# MyMultisensors_rev1-1.net
KiCad netlist of a schematic drawn in EAGLE
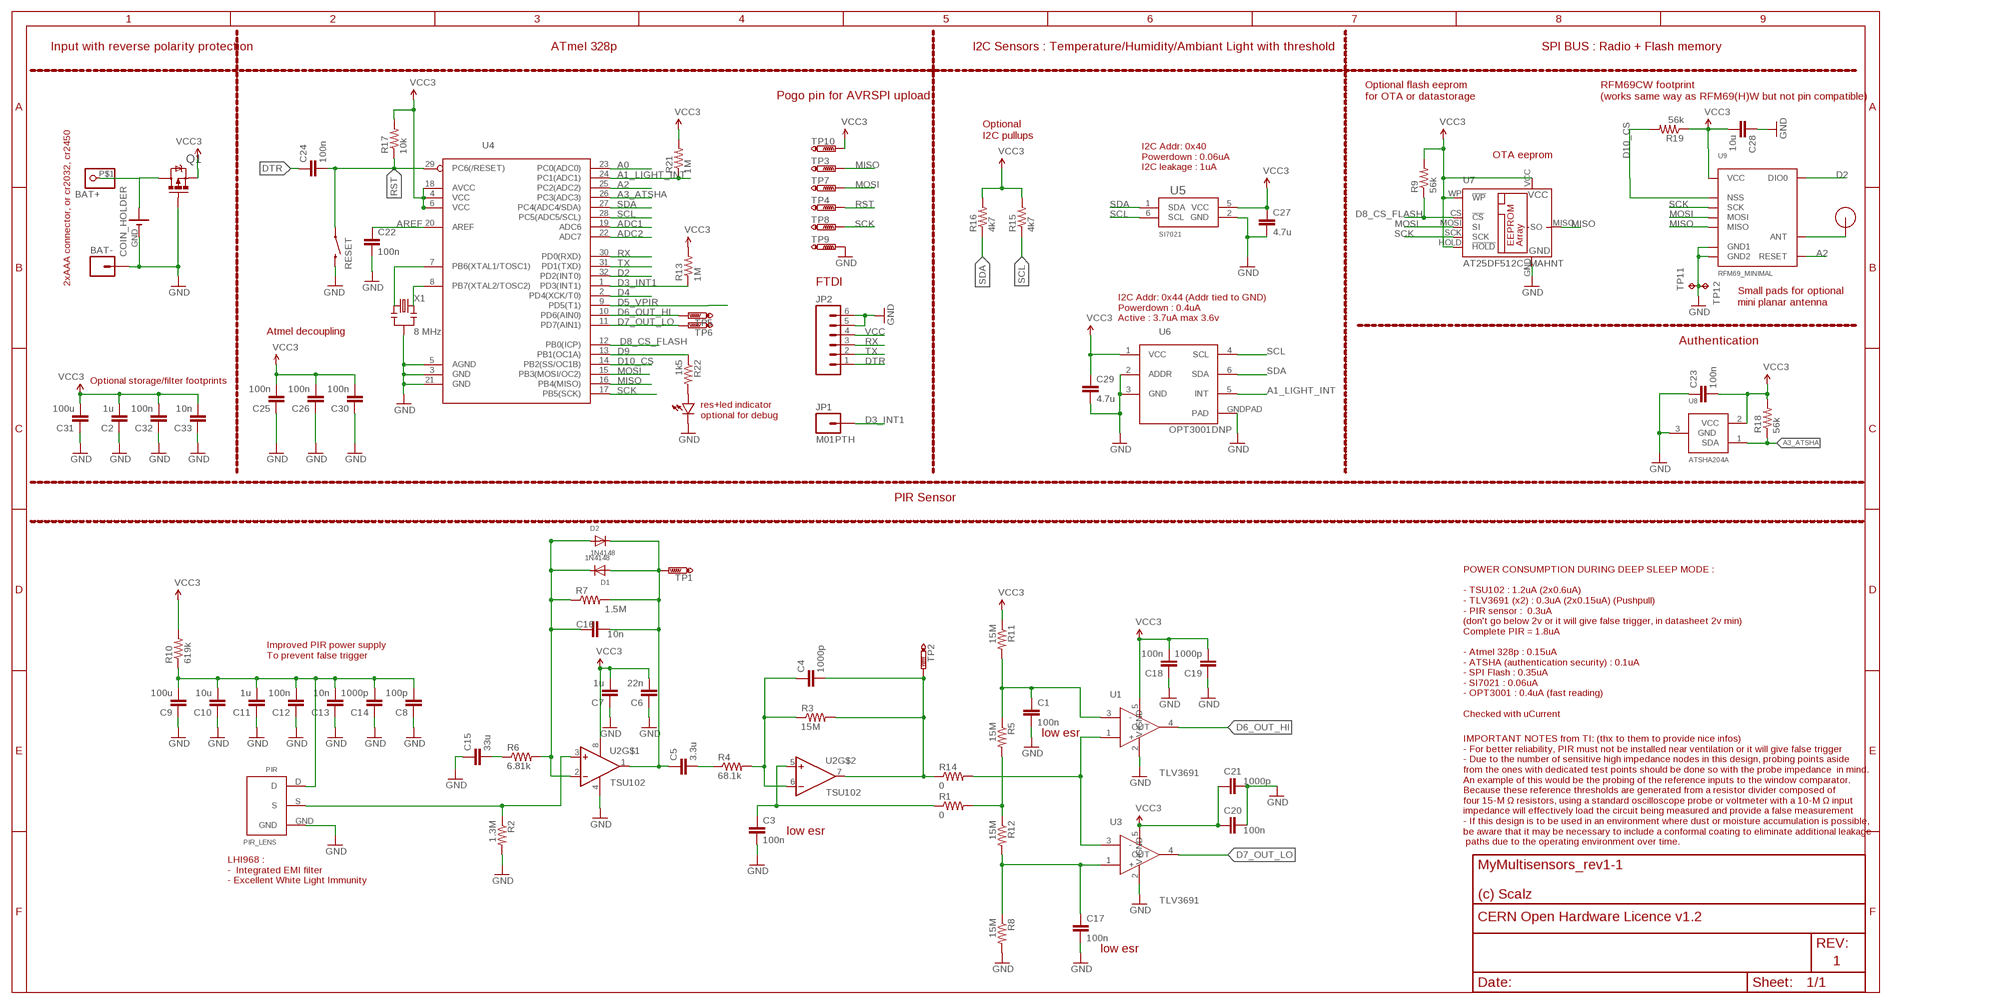
[diagram p0: schematic, sheet 1]

(export (version "E")
  (design (tool "Eeschema 10.0.6"))
  (components
    (comp (ref "ANT")
      (value "RFM12B_ANTENNA")
      (footprint "eagle-import:RFM12B-ANTENNA")
      (libsource (lib "eagle-import") (part "RFM12B_ANTENNA"))
    )
    (comp (ref "BAT+")
      (value "PINHD-1X1TOP")
      (footprint "eagle-import:1X01_ONESIDE")
      (libsource (lib "eagle-import") (part "PINHD-1X1TOP"))
    )
    (comp (ref "BAT-")
      (value "M01PTH")
      (footprint "eagle-import:1X01")
      (libsource (lib "eagle-import") (part "M01PTH"))
    )
    (comp (ref "C1")
      (value "100n")
      (footprint "eagle-import:0603-CAP")
      (libsource (lib "eagle-import") (part "CAP0603-CAP"))
    )
    (comp (ref "C2")
      (value "1u")
      (footprint "eagle-import:0805-CAP")
      (libsource (lib "eagle-import") (part "CAP0805-CAP"))
    )
    (comp (ref "C3")
      (value "100n")
      (footprint "eagle-import:0603-CAP")
      (libsource (lib "eagle-import") (part "CAP0603-CAP"))
    )
    (comp (ref "C4")
      (value "1000p")
      (footprint "eagle-import:0603-CAP")
      (libsource (lib "eagle-import") (part "CAP0603-CAP"))
    )
    (comp (ref "C5")
      (value "3.3u")
      (footprint "eagle-import:0603-CAP")
      (libsource (lib "eagle-import") (part "CAP0603-CAP"))
    )
    (comp (ref "C6")
      (value "22n")
      (footprint "eagle-import:0603-CAP")
      (libsource (lib "eagle-import") (part "CAP0603-CAP"))
    )
    (comp (ref "C7")
      (value "1u")
      (footprint "eagle-import:0603-CAP")
      (libsource (lib "eagle-import") (part "CAP0603-CAP"))
    )
    (comp (ref "C8")
      (value "100p")
      (footprint "eagle-import:0603-CAP")
      (libsource (lib "eagle-import") (part "CAP0603-CAP"))
    )
    (comp (ref "C9")
      (value "100u")
      (footprint "eagle-import:0805-CAP")
      (libsource (lib "eagle-import") (part "CAP0805-CAP"))
    )
    (comp (ref "C10")
      (value "10u")
      (footprint "eagle-import:0805-CAP")
      (libsource (lib "eagle-import") (part "CAP0805-CAP"))
    )
    (comp (ref "C11")
      (value "1u")
      (footprint "eagle-import:0603-CAP")
      (libsource (lib "eagle-import") (part "CAP0603-CAP"))
    )
    (comp (ref "C12")
      (value "100n")
      (footprint "eagle-import:0603-CAP")
      (libsource (lib "eagle-import") (part "CAP0603-CAP"))
    )
    (comp (ref "C13")
      (value "10n")
      (footprint "eagle-import:0603-CAP")
      (libsource (lib "eagle-import") (part "CAP0603-CAP"))
    )
    (comp (ref "C14")
      (value "1000p")
      (footprint "eagle-import:0603-CAP")
      (libsource (lib "eagle-import") (part "CAP0603-CAP"))
    )
    (comp (ref "C15")
      (value "33u")
      (footprint "eagle-import:0805-CAP")
      (libsource (lib "eagle-import") (part "CAP0805-CAP"))
    )
    (comp (ref "C16")
      (value "10n")
      (footprint "eagle-import:0603-CAP")
      (libsource (lib "eagle-import") (part "CAP0603-CAP"))
    )
    (comp (ref "C17")
      (value "100n")
      (footprint "eagle-import:0603-CAP")
      (libsource (lib "eagle-import") (part "CAP0603-CAP"))
    )
    (comp (ref "C18")
      (value "100n")
      (footprint "eagle-import:0603-CAP")
      (libsource (lib "eagle-import") (part "CAP0603-CAP"))
    )
    (comp (ref "C19")
      (value "1000p")
      (footprint "eagle-import:0603-CAP")
      (libsource (lib "eagle-import") (part "CAP0603-CAP"))
    )
    (comp (ref "C20")
      (value "100n")
      (footprint "eagle-import:0603-CAP")
      (libsource (lib "eagle-import") (part "CAP0603-CAP"))
    )
    (comp (ref "C21")
      (value "1000p")
      (footprint "eagle-import:0603-CAP")
      (libsource (lib "eagle-import") (part "CAP0603-CAP"))
    )
    (comp (ref "C22")
      (value "100n")
      (footprint "eagle-import:0603-CAP")
      (libsource (lib "eagle-import") (part "CAP0603-CAP"))
    )
    (comp (ref "C23")
      (value "100n")
      (footprint "eagle-import:0603-CAP")
      (libsource (lib "eagle-import") (part "CAP0603-CAP"))
    )
    (comp (ref "C24")
      (value "100n")
      (footprint "eagle-import:0805-CAP")
      (libsource (lib "eagle-import") (part "CAP0805-CAP"))
    )
    (comp (ref "C25")
      (value "100n")
      (footprint "eagle-import:0603-CAP")
      (libsource (lib "eagle-import") (part "CAP0603-CAP"))
    )
    (comp (ref "C26")
      (value "100n")
      (footprint "eagle-import:0603-CAP")
      (libsource (lib "eagle-import") (part "CAP0603-CAP"))
    )
    (comp (ref "C27")
      (value "4.7u")
      (footprint "eagle-import:0603-CAP")
      (libsource (lib "eagle-import") (part "CAP0603-CAP"))
    )
    (comp (ref "C28")
      (value "10u")
      (footprint "eagle-import:0805-CAP")
      (libsource (lib "eagle-import") (part "CAP0805-CAP"))
    )
    (comp (ref "C29")
      (value "4.7u")
      (footprint "eagle-import:0603-CAP")
      (libsource (lib "eagle-import") (part "CAP0603-CAP"))
    )
    (comp (ref "C30")
      (value "100n")
      (footprint "eagle-import:0603-CAP")
      (libsource (lib "eagle-import") (part "CAP0603-CAP"))
    )
    (comp (ref "C31")
      (value "100u")
      (footprint "eagle-import:0805-CAP")
      (libsource (lib "eagle-import") (part "CAP0805-CAP"))
    )
    (comp (ref "C32")
      (value "100n")
      (footprint "eagle-import:0603-CAP")
      (libsource (lib "eagle-import") (part "CAP0603-CAP"))
    )
    (comp (ref "C33")
      (value "10n")
      (footprint "eagle-import:0603-CAP")
      (libsource (lib "eagle-import") (part "CAP0603-CAP"))
    )
    (comp (ref "COIN_HOLDER")
      (value "CR2450_H_LOWCOSTVERTICAL_WITH_MILL")
      (footprint "eagle-import:CR2450H_LOWCOST2")
      (libsource (lib "eagle-import") (part "CR2450_H_LOWCOSTVERTICAL_WITH_MILL"))
    )
    (comp (ref "D1")
      (value "1N4148")
      (footprint "eagle-import:SOD-123")
      (libsource (lib "eagle-import") (part "DIODESOD-123"))
    )
    (comp (ref "D2")
      (value "1N4148")
      (footprint "eagle-import:SOD-123")
      (libsource (lib "eagle-import") (part "DIODESOD-123"))
    )
    (comp (ref "D3")
      (value "LED0805")
      (footprint "eagle-import:0805-LED")
      (libsource (lib "eagle-import") (part "LED0805"))
    )
    (comp (ref "JP1")
      (value "M01PTH")
      (footprint "eagle-import:1X01")
      (libsource (lib "eagle-import") (part "M01PTH"))
    )
    (comp (ref "JP2")
      (value "M06SIP")
      (footprint "eagle-import:1X06")
      (libsource (lib "eagle-import") (part "M06SIP"))
    )
    (comp (ref "PIR")
      (value "PIR_LENS")
      (footprint "eagle-import:PIR_LENS")
      (libsource (lib "eagle-import") (part "PIR_LENS"))
    )
    (comp (ref "Q1")
      (value "SI2399DS-T1-GE3")
      (footprint "eagle-import:SOT95P237X112-3N")
      (libsource (lib "eagle-import") (part "SI2399DS-T1-GE3"))
    )
    (comp (ref "R1")
      (value "0")
      (footprint "eagle-import:0603-RES")
      (libsource (lib "eagle-import") (part "RESISTOR0603-RES"))
    )
    (comp (ref "R2")
      (value "1.3M")
      (footprint "eagle-import:0603-RES")
      (libsource (lib "eagle-import") (part "RESISTOR0603-RES"))
    )
    (comp (ref "R3")
      (value "15M")
      (footprint "eagle-import:0603-RES")
      (libsource (lib "eagle-import") (part "RESISTOR0603-RES"))
    )
    (comp (ref "R4")
      (value "68.1k")
      (footprint "eagle-import:0603-RES")
      (libsource (lib "eagle-import") (part "RESISTOR0603-RES"))
    )
    (comp (ref "R5")
      (value "15M")
      (footprint "eagle-import:0603-RES")
      (libsource (lib "eagle-import") (part "RESISTOR0603-RES"))
    )
    (comp (ref "R6")
      (value "6.81k")
      (footprint "eagle-import:0603-RES")
      (libsource (lib "eagle-import") (part "RESISTOR0603-RES"))
    )
    (comp (ref "R7")
      (value "1.5M")
      (footprint "eagle-import:0603-RES")
      (libsource (lib "eagle-import") (part "RESISTOR0603-RES"))
    )
    (comp (ref "R8")
      (value "15M")
      (footprint "eagle-import:0603-RES")
      (libsource (lib "eagle-import") (part "RESISTOR0603-RES"))
    )
    (comp (ref "R9")
      (value "56k")
      (footprint "eagle-import:0603-RES")
      (libsource (lib "eagle-import") (part "RESISTOR0603-RES"))
    )
    (comp (ref "R10")
      (value "619k")
      (footprint "eagle-import:0603-RES")
      (libsource (lib "eagle-import") (part "RESISTOR0603-RES"))
    )
    (comp (ref "R11")
      (value "15M")
      (footprint "eagle-import:0603-RES")
      (libsource (lib "eagle-import") (part "RESISTOR0603-RES"))
    )
    (comp (ref "R12")
      (value "15M")
      (footprint "eagle-import:0603-RES")
      (libsource (lib "eagle-import") (part "RESISTOR0603-RES"))
    )
    (comp (ref "R13")
      (value "1M")
      (footprint "eagle-import:0603-RES")
      (libsource (lib "eagle-import") (part "RESISTOR0603-RES"))
    )
    (comp (ref "R14")
      (value "0")
      (footprint "eagle-import:0603-RES")
      (libsource (lib "eagle-import") (part "RESISTOR0603-RES"))
    )
    (comp (ref "R15")
      (value "4k7")
      (footprint "eagle-import:0603-RES")
      (libsource (lib "eagle-import") (part "RESISTOR0603-RES"))
    )
    (comp (ref "R16")
      (value "4k7")
      (footprint "eagle-import:0603-RES")
      (libsource (lib "eagle-import") (part "RESISTOR0603-RES"))
    )
    (comp (ref "R17")
      (value "10k")
      (footprint "eagle-import:0805-RES")
      (libsource (lib "eagle-import") (part "RESISTOR0805-RES"))
    )
    (comp (ref "R18")
      (value "56k")
      (footprint "eagle-import:0603-RES")
      (libsource (lib "eagle-import") (part "RESISTOR0603-RES"))
    )
    (comp (ref "R19")
      (value "56k")
      (footprint "eagle-import:0603-RES")
      (libsource (lib "eagle-import") (part "RESISTOR0603-RES"))
    )
    (comp (ref "R21")
      (value "1M")
      (footprint "eagle-import:0603-RES")
      (libsource (lib "eagle-import") (part "RESISTOR0603-RES"))
    )
    (comp (ref "R22")
      (value "1k5")
      (footprint "eagle-import:0603-RES")
      (libsource (lib "eagle-import") (part "RESISTOR0603-RES"))
    )
    (comp (ref "RESET")
      (value "SWITCH-MOMENTARY-2-SMD-1101NE")
      (footprint "eagle-import:TACTILE-SWITCH-1101NE")
      (libsource (lib "eagle-import") (part "SWITCH-MOMENTARY-2-SMD-1101NE"))
    )
    (comp (ref "TP1")
      (value "PTR1B1,27")
      (footprint "eagle-import:B1,27")
      (libsource (lib "eagle-import") (part "PTR1B1,27"))
    )
    (comp (ref "TP2")
      (value "PTR1B1,27")
      (footprint "eagle-import:B1,27")
      (libsource (lib "eagle-import") (part "PTR1B1,27"))
    )
    (comp (ref "TP3")
      (value "PTR1TP18R")
      (footprint "eagle-import:TP18R")
      (libsource (lib "eagle-import") (part "PTR1TP18R"))
    )
    (comp (ref "TP4")
      (value "PTR1TP18R")
      (footprint "eagle-import:TP18R")
      (libsource (lib "eagle-import") (part "PTR1TP18R"))
    )
    (comp (ref "TP5")
      (value "PTR1B1,27")
      (footprint "eagle-import:B1,27")
      (libsource (lib "eagle-import") (part "PTR1B1,27"))
    )
    (comp (ref "TP6")
      (value "PTR1B1,27")
      (footprint "eagle-import:B1,27")
      (libsource (lib "eagle-import") (part "PTR1B1,27"))
    )
    (comp (ref "TP7")
      (value "PTR1TP18R")
      (footprint "eagle-import:TP18R")
      (libsource (lib "eagle-import") (part "PTR1TP18R"))
    )
    (comp (ref "TP8")
      (value "PTR1TP18R")
      (footprint "eagle-import:TP18R")
      (libsource (lib "eagle-import") (part "PTR1TP18R"))
    )
    (comp (ref "TP9")
      (value "PTR1TP18R")
      (footprint "eagle-import:TP18R")
      (libsource (lib "eagle-import") (part "PTR1TP18R"))
    )
    (comp (ref "TP10")
      (value "PTR1TP18R")
      (footprint "eagle-import:TP18R")
      (libsource (lib "eagle-import") (part "PTR1TP18R"))
    )
    (comp (ref "TP11")
      (value "TPTP10SQ")
      (footprint "eagle-import:TP10SQ")
      (libsource (lib "eagle-import") (part "TPTP10SQ"))
    )
    (comp (ref "TP12")
      (value "TPTP10SQ")
      (footprint "eagle-import:TP10SQ")
      (libsource (lib "eagle-import") (part "TPTP10SQ"))
    )
    (comp (ref "U1")
      (value "TLV3691")
      (footprint "eagle-import:SC70-5")
      (libsource (lib "eagle-import") (part "TLV3691"))
    )
    (comp (ref "U2")
      (value "TSU102")
      (footprint "eagle-import:MINI_SO8")
      (libsource (lib "eagle-import") (part "TSU102"))
    )
    (comp (ref "U3")
      (value "TLV3691")
      (footprint "eagle-import:SC70-5")
      (libsource (lib "eagle-import") (part "TLV3691"))
    )
    (comp (ref "U4")
      (value "ATMega-328")
      (footprint "eagle-import:TQFP32-08")
      (libsource (lib "eagle-import") (part "ATMEGA168/328TQFP32"))
    )
    (comp (ref "U5")
      (value "SI7021")
      (footprint "eagle-import:DFN6")
      (libsource (lib "eagle-import") (part "SI7021"))
    )
    (comp (ref "U6")
      (value "OPT3001DNP")
      (footprint "eagle-import:OPT3001DNP")
      (libsource (lib "eagle-import") (part "OPT3001DNP"))
    )
    (comp (ref "U7")
      (value "AT25DF512C_MAHNT")
      (footprint "eagle-import:AT25DF512C_MAHNT")
      (libsource (lib "eagle-import") (part "AT25DF512C_MAHNT"))
    )
    (comp (ref "U8")
      (value "ATSHA204A")
      (footprint "eagle-import:SOT23")
      (libsource (lib "eagle-import") (part "ATSHA204A"))
    )
    (comp (ref "U9")
      (value "RFM69_MINIMAL")
      (footprint "eagle-import:RFM69CW_MINIMAL")
      (libsource (lib "eagle-import") (part "RFM69_MINIMAL"))
    )
    (comp (ref "X1")
      (value "8 MHz")
      (footprint "eagle-import:RESONATOR-SMD")
      (libsource (lib "eagle-import") (part "RESONATORSMD"))
    )
  )
  (nets
    (net (code "1") (name "/A0") (class "Default")
      (node (ref "U4") (pin "23") (pinfunction "PC0(ADC0)_23") (pintype "bidirectional"))
    )
    (net (code "2") (name "/A1_LIGHT_INT") (class "Default")
      (node (ref "R21") (pin "1") (pinfunction "1_1") (pintype "passive"))
      (node (ref "U4") (pin "24") (pinfunction "PC1(ADC1)_24") (pintype "bidirectional"))
      (node (ref "U6") (pin "5") (pinfunction "INT_5") (pintype "bidirectional"))
    )
    (net (code "3") (name "/A2") (class "Default")
      (node (ref "U4") (pin "25") (pinfunction "PC2(ADC2)_25") (pintype "bidirectional"))
      (node (ref "U9") (pin "RESET") (pinfunction "RESET_RESET") (pintype "bidirectional"))
    )
    (net (code "4") (name "/ADC1") (class "Default")
      (node (ref "U4") (pin "19") (pinfunction "ADC6_19") (pintype "bidirectional"))
    )
    (net (code "5") (name "/ADC2") (class "Default")
      (node (ref "U4") (pin "22") (pinfunction "ADC7_22") (pintype "bidirectional"))
    )
    (net (code "6") (name "/AREF") (class "Default")
      (node (ref "C22") (pin "1") (pinfunction "1_1") (pintype "passive"))
      (node (ref "U4") (pin "20") (pinfunction "AREF_20") (pintype "bidirectional"))
    )
    (net (code "7") (name "/D2") (class "Default")
      (node (ref "U4") (pin "32") (pinfunction "PD2(INT0)_32") (pintype "bidirectional"))
      (node (ref "U9") (pin "DIO0") (pinfunction "DIO0_DIO0") (pintype "open_collector"))
    )
    (net (code "8") (name "/D3_INT1") (class "Default")
      (node (ref "JP1") (pin "1") (pinfunction "1_1") (pintype "passive"))
      (node (ref "R13") (pin "1") (pinfunction "1_1") (pintype "passive"))
      (node (ref "U4") (pin "1") (pinfunction "PD3(INT1)_1") (pintype "bidirectional"))
    )
    (net (code "9") (name "/D4") (class "Default")
      (node (ref "U4") (pin "2") (pinfunction "PD4(XCK/T0)_2") (pintype "bidirectional"))
    )
    (net (code "10") (name "/D5_VPIR") (class "Default")
      (node (ref "U4") (pin "9") (pinfunction "PD5(T1)_9") (pintype "bidirectional"))
    )
    (net (code "11") (name "/D8_CS_FLASH") (class "Default")
      (node (ref "R9") (pin "1") (pinfunction "1_1") (pintype "passive"))
      (node (ref "U4") (pin "12") (pinfunction "PB0(ICP)_12") (pintype "bidirectional"))
      (node (ref "U7") (pin "CS") (pinfunction "~{CS}_CS") (pintype "input"))
    )
    (net (code "12") (name "/D9") (class "Default")
      (node (ref "R22") (pin "1") (pinfunction "1_1") (pintype "passive"))
      (node (ref "U4") (pin "13") (pinfunction "PB1(OC1A)_13") (pintype "bidirectional"))
    )
    (net (code "13") (name "/D10_CS") (class "Default")
      (node (ref "R19") (pin "2") (pinfunction "2_2") (pintype "passive"))
      (node (ref "U4") (pin "14") (pinfunction "PB2(SS/OC1B)_14") (pintype "bidirectional"))
      (node (ref "U9") (pin "NSS") (pinfunction "NSS_NSS") (pintype "input"))
    )
    (net (code "14") (name "/MISO") (class "Default")
      (node (ref "TP3") (pin "TP") (pinfunction "TP_TP") (pintype "input"))
      (node (ref "U4") (pin "16") (pinfunction "PB4(MISO)_16") (pintype "bidirectional"))
      (node (ref "U7") (pin "MISO") (pinfunction "SO_MISO") (pintype "bidirectional"))
      (node (ref "U9") (pin "MISO") (pinfunction "MISO_MISO") (pintype "output"))
    )
    (net (code "15") (name "/MOSI") (class "Default")
      (node (ref "TP7") (pin "TP") (pinfunction "TP_TP") (pintype "input"))
      (node (ref "U4") (pin "15") (pinfunction "PB3(MOSI/OC2)_15") (pintype "bidirectional"))
      (node (ref "U7") (pin "MOSI") (pinfunction "SI_MOSI") (pintype "input"))
      (node (ref "U9") (pin "MOSI") (pinfunction "MOSI_MOSI") (pintype "input"))
    )
    (net (code "16") (name "/N$3") (class "Default")
      (node (ref "PIR") (pin "S") (pinfunction "S_S") (pintype "bidirectional"))
      (node (ref "R2") (pin "1") (pinfunction "1_1") (pintype "passive"))
      (node (ref "U2") (pin "3") (pinfunction "+IN_3") (pintype "input"))
    )
    (net (code "17") (name "/RX") (class "Default")
      (node (ref "JP2") (pin "3") (pinfunction "3_3") (pintype "passive"))
      (node (ref "U4") (pin "30") (pinfunction "PD0(RXD)_30") (pintype "bidirectional"))
    )
    (net (code "18") (name "/SCK") (class "Default")
      (node (ref "TP8") (pin "TP") (pinfunction "TP_TP") (pintype "input"))
      (node (ref "U4") (pin "17") (pinfunction "PB5(SCK)_17") (pintype "bidirectional"))
      (node (ref "U7") (pin "SCK") (pinfunction "SCK_SCK") (pintype "input"))
      (node (ref "U9") (pin "SCK") (pinfunction "SCK_SCK") (pintype "input"))
    )
    (net (code "19") (name "/TX") (class "Default")
      (node (ref "JP2") (pin "2") (pinfunction "2_2") (pintype "passive"))
      (node (ref "U4") (pin "31") (pinfunction "PD1(TXD)_31") (pintype "bidirectional"))
    )
    (net (code "20") (name "A3_ATSHA") (class "Default")
      (node (ref "R18") (pin "1") (pinfunction "1_1") (pintype "passive"))
      (node (ref "U4") (pin "26") (pinfunction "PC3(ADC3)_26") (pintype "bidirectional"))
      (node (ref "U8") (pin "1") (pinfunction "SDA_1") (pintype "bidirectional"))
    )
    (net (code "21") (name "D6_OUT_HI") (class "Default")
      (node (ref "TP5") (pin "TP") (pinfunction "TP_TP") (pintype "input"))
      (node (ref "U1") (pin "4") (pinfunction "OUT_4") (pintype "bidirectional"))
      (node (ref "U4") (pin "10") (pinfunction "PD6(AIN0)_10") (pintype "bidirectional"))
    )
    (net (code "22") (name "D7_OUT_LO") (class "Default")
      (node (ref "TP6") (pin "TP") (pinfunction "TP_TP") (pintype "input"))
      (node (ref "U3") (pin "4") (pinfunction "OUT_4") (pintype "bidirectional"))
      (node (ref "U4") (pin "11") (pinfunction "PD7(AIN1)_11") (pintype "bidirectional"))
    )
    (net (code "23") (name "DTR") (class "Default")
      (node (ref "C24") (pin "1") (pinfunction "1_1") (pintype "passive"))
      (node (ref "JP2") (pin "1") (pinfunction "1_1") (pintype "passive"))
    )
    (net (code "24") (name "GND") (class "Default")
      (node (ref "BAT-") (pin "1") (pinfunction "1_1") (pintype "passive"))
      (node (ref "C1") (pin "2") (pinfunction "2_2") (pintype "passive"))
      (node (ref "C10") (pin "1") (pinfunction "1_1") (pintype "passive"))
      (node (ref "C11") (pin "1") (pinfunction "1_1") (pintype "passive"))
      (node (ref "C12") (pin "1") (pinfunction "1_1") (pintype "passive"))
      (node (ref "C13") (pin "1") (pinfunction "1_1") (pintype "passive"))
      (node (ref "C14") (pin "1") (pinfunction "1_1") (pintype "passive"))
      (node (ref "C15") (pin "1") (pinfunction "1_1") (pintype "passive"))
      (node (ref "C17") (pin "2") (pinfunction "2_2") (pintype "passive"))
      (node (ref "C18") (pin "1") (pinfunction "1_1") (pintype "passive"))
      (node (ref "C19") (pin "1") (pinfunction "1_1") (pintype "passive"))
      (node (ref "C2") (pin "1") (pinfunction "1_1") (pintype "passive"))
      (node (ref "C20") (pin "1") (pinfunction "1_1") (pintype "passive"))
      (node (ref "C21") (pin "1") (pinfunction "1_1") (pintype "passive"))
      (node (ref "C22") (pin "2") (pinfunction "2_2") (pintype "passive"))
      (node (ref "C23") (pin "1") (pinfunction "1_1") (pintype "passive"))
      (node (ref "C25") (pin "1") (pinfunction "1_1") (pintype "passive"))
      (node (ref "C26") (pin "1") (pinfunction "1_1") (pintype "passive"))
      (node (ref "C27") (pin "2") (pinfunction "2_2") (pintype "passive"))
      (node (ref "C28") (pin "1") (pinfunction "1_1") (pintype "passive"))
      (node (ref "C29") (pin "2") (pinfunction "2_2") (pintype "passive"))
      (node (ref "C3") (pin "2") (pinfunction "2_2") (pintype "passive"))
      (node (ref "C30") (pin "1") (pinfunction "1_1") (pintype "passive"))
      (node (ref "C31") (pin "1") (pinfunction "1_1") (pintype "passive"))
      (node (ref "C32") (pin "1") (pinfunction "1_1") (pintype "passive"))
      (node (ref "C33") (pin "1") (pinfunction "1_1") (pintype "passive"))
      (node (ref "C6") (pin "1") (pinfunction "1_1") (pintype "passive"))
      (node (ref "C7") (pin "1") (pinfunction "1_1") (pintype "passive"))
      (node (ref "C8") (pin "1") (pinfunction "1_1") (pintype "passive"))
      (node (ref "C9") (pin "1") (pinfunction "1_1") (pintype "passive"))
      (node (ref "COIN_HOLDER") (pin "GND") (pinfunction "-_GND") (pintype "passive"))
      (node (ref "D3") (pin "MINUS") (pinfunction "MINUS_MINUS") (pintype "passive"))
      (node (ref "JP2") (pin "5") (pinfunction "5_5") (pintype "passive"))
      (node (ref "JP2") (pin "6") (pinfunction "6_6") (pintype "passive"))
      (node (ref "PIR") (pin "GND") (pinfunction "GND_GND") (pintype "bidirectional"))
      (node (ref "Q1") (pin "1") (pinfunction "G_1") (pintype "passive"))
      (node (ref "R2") (pin "2") (pinfunction "2_2") (pintype "passive"))
      (node (ref "R8") (pin "2") (pinfunction "2_2") (pintype "passive"))
      (node (ref "RESET") (pin "P$2") (pinfunction "2_P$2") (pintype "passive"))
      (node (ref "TP11") (pin "TP") (pinfunction "TP_TP") (pintype "input"))
      (node (ref "TP12") (pin "TP") (pinfunction "TP_TP") (pintype "input"))
      (node (ref "TP9") (pin "TP") (pinfunction "TP_TP") (pintype "input"))
      (node (ref "U1") (pin "2") (pinfunction "GND_2") (pintype "bidirectional"))
      (node (ref "U2") (pin "4") (pinfunction "V-_4") (pintype "power_in"))
      (node (ref "U3") (pin "2") (pinfunction "GND_2") (pintype "bidirectional"))
      (node (ref "U4") (pin "21") (pinfunction "GND_21") (pintype "bidirectional"))
      (node (ref "U4") (pin "3") (pinfunction "GND_3") (pintype "bidirectional"))
      (node (ref "U4") (pin "5") (pinfunction "AGND_5") (pintype "bidirectional"))
      (node (ref "U5") (pin "2") (pinfunction "GND_2") (pintype "bidirectional"))
      (node (ref "U6") (pin "2") (pinfunction "ADDR_2") (pintype "bidirectional"))
      (node (ref "U6") (pin "3") (pinfunction "GND_3") (pintype "bidirectional"))
      (node (ref "U6") (pin "GNDPAD") (pinfunction "PAD_GNDPAD") (pintype "bidirectional"))
      (node (ref "U7") (pin "GND") (pinfunction "GND_GND") (pintype "power_in"))
      (node (ref "U8") (pin "3") (pinfunction "GND_3") (pintype "bidirectional"))
      (node (ref "U9") (pin "GND") (pinfunction "GND1_GND") (pintype "power_in"))
      (node (ref "U9") (pin "GND2") (pinfunction "GND2_GND2") (pintype "power_in"))
      (node (ref "X1") (pin "2") (pinfunction "2_2") (pintype "passive"))
    )
    (net (code "25") (name "Net-(ANT-1)") (class "Default")
      (node (ref "ANT") (pin "P$1") (pinfunction "1_P$1") (pintype "bidirectional"))
      (node (ref "U9") (pin "ANT") (pinfunction "ANT_ANT") (pintype "passive"))
    )
    (net (code "26") (name "Net-(BAT+-1)") (class "Default")
      (node (ref "BAT+") (pin "P$1") (pinfunction "1_P$1") (pintype "passive"))
      (node (ref "COIN_HOLDER") (pin "VBAT@1") (pinfunction "+_VBAT@1") (pintype "passive"))
      (node (ref "COIN_HOLDER") (pin "VBAT@2") (pinfunction "+_VBAT@2") (pintype "passive"))
      (node (ref "COIN_HOLDER") (pin "VBAT@3") (pinfunction "+_VBAT@3") (pintype "passive"))
      (node (ref "COIN_HOLDER") (pin "VBAT@4") (pinfunction "+_VBAT@4") (pintype "passive"))
      (node (ref "Q1") (pin "3") (pinfunction "D_3") (pintype "passive"))
    )
    (net (code "27") (name "Net-(C5-Pad2)") (class "Default")
      (node (ref "C5") (pin "2") (pinfunction "2_2") (pintype "passive"))
      (node (ref "R4") (pin "1") (pinfunction "1_1") (pintype "passive"))
    )
    (net (code "28") (name "Net-(C10-Pad2)") (class "Default")
      (node (ref "C10") (pin "2") (pinfunction "2_2") (pintype "passive"))
      (node (ref "C11") (pin "2") (pinfunction "2_2") (pintype "passive"))
      (node (ref "C12") (pin "2") (pinfunction "2_2") (pintype "passive"))
      (node (ref "C13") (pin "2") (pinfunction "2_2") (pintype "passive"))
      (node (ref "C14") (pin "2") (pinfunction "2_2") (pintype "passive"))
      (node (ref "C8") (pin "2") (pinfunction "2_2") (pintype "passive"))
      (node (ref "C9") (pin "2") (pinfunction "2_2") (pintype "passive"))
      (node (ref "PIR") (pin "D") (pinfunction "D_D") (pintype "bidirectional"))
      (node (ref "R10") (pin "1") (pinfunction "1_1") (pintype "passive"))
    )
    (net (code "29") (name "Net-(C15-Pad2)") (class "Default")
      (node (ref "C15") (pin "2") (pinfunction "2_2") (pintype "passive"))
      (node (ref "R6") (pin "1") (pinfunction "1_1") (pintype "passive"))
    )
    (net (code "30") (name "Net-(D3-PadPLUS)") (class "Default")
      (node (ref "D3") (pin "PLUS") (pinfunction "PLUS_PLUS") (pintype "passive"))
      (node (ref "R22") (pin "2") (pinfunction "2_2") (pintype "passive"))
    )
    (net (code "31") (name "Net-(R1-Pad2)") (class "Default")
      (node (ref "R1") (pin "2") (pinfunction "2_2") (pintype "passive"))
      (node (ref "R12") (pin "1") (pinfunction "1_1") (pintype "passive"))
      (node (ref "R5") (pin "2") (pinfunction "2_2") (pintype "passive"))
    )
    (net (code "32") (name "Net-(U1-+)") (class "Default")
      (node (ref "R14") (pin "2") (pinfunction "2_2") (pintype "passive"))
      (node (ref "U1") (pin "1") (pinfunction "+_1") (pintype "bidirectional"))
      (node (ref "U3") (pin "3") (pinfunction "-_3") (pintype "bidirectional"))
    )
    (net (code "33") (name "Net-(U1--)") (class "Default")
      (node (ref "C1") (pin "1") (pinfunction "1_1") (pintype "passive"))
      (node (ref "R11") (pin "2") (pinfunction "2_2") (pintype "passive"))
      (node (ref "R5") (pin "1") (pinfunction "1_1") (pintype "passive"))
      (node (ref "U1") (pin "3") (pinfunction "-_3") (pintype "bidirectional"))
    )
    (net (code "34") (name "Net-(U2A--IN)") (class "Default")
      (node (ref "C16") (pin "1") (pinfunction "1_1") (pintype "passive"))
      (node (ref "D1") (pin "C") (pinfunction "C_C") (pintype "passive"))
      (node (ref "D2") (pin "A") (pinfunction "A_A") (pintype "passive"))
      (node (ref "R6") (pin "2") (pinfunction "2_2") (pintype "passive"))
      (node (ref "R7") (pin "1") (pinfunction "1_1") (pintype "passive"))
      (node (ref "U2") (pin "2") (pinfunction "-IN_2") (pintype "input"))
    )
    (net (code "35") (name "Net-(U2A-OUT)") (class "Default")
      (node (ref "C16") (pin "2") (pinfunction "2_2") (pintype "passive"))
      (node (ref "C5") (pin "1") (pinfunction "1_1") (pintype "passive"))
      (node (ref "D1") (pin "A") (pinfunction "A_A") (pintype "passive"))
      (node (ref "D2") (pin "C") (pinfunction "C_C") (pintype "passive"))
      (node (ref "R7") (pin "2") (pinfunction "2_2") (pintype "passive"))
      (node (ref "TP1") (pin "TP") (pinfunction "TP_TP") (pintype "input"))
      (node (ref "U2") (pin "1") (pinfunction "OUT_1") (pintype "output"))
    )
    (net (code "36") (name "Net-(U2B-+IN)") (class "Default")
      (node (ref "C3") (pin "1") (pinfunction "1_1") (pintype "passive"))
      (node (ref "R1") (pin "1") (pinfunction "1_1") (pintype "passive"))
      (node (ref "U2") (pin "5") (pinfunction "+IN_5") (pintype "input"))
    )
    (net (code "37") (name "Net-(U2B--IN)") (class "Default")
      (node (ref "C4") (pin "1") (pinfunction "1_1") (pintype "passive"))
      (node (ref "R3") (pin "1") (pinfunction "1_1") (pintype "passive"))
      (node (ref "R4") (pin "2") (pinfunction "2_2") (pintype "passive"))
      (node (ref "U2") (pin "6") (pinfunction "-IN_6") (pintype "input"))
    )
    (net (code "38") (name "Net-(U2B-OUT)") (class "Default")
      (node (ref "C4") (pin "2") (pinfunction "2_2") (pintype "passive"))
      (node (ref "R14") (pin "1") (pinfunction "1_1") (pintype "passive"))
      (node (ref "R3") (pin "2") (pinfunction "2_2") (pintype "passive"))
      (node (ref "TP2") (pin "TP") (pinfunction "TP_TP") (pintype "input"))
      (node (ref "U2") (pin "7") (pinfunction "OUT_7") (pintype "output"))
    )
    (net (code "39") (name "Net-(U3-+)") (class "Default")
      (node (ref "C17") (pin "1") (pinfunction "1_1") (pintype "passive"))
      (node (ref "R12") (pin "2") (pinfunction "2_2") (pintype "passive"))
      (node (ref "R8") (pin "1") (pinfunction "1_1") (pintype "passive"))
      (node (ref "U3") (pin "1") (pinfunction "+_1") (pintype "bidirectional"))
    )
    (net (code "40") (name "Net-(U4-PB6(XTAL1{slash}TOSC1))") (class "Default")
      (node (ref "U4") (pin "7") (pinfunction "PB6(XTAL1/TOSC1)_7") (pintype "bidirectional"))
      (node (ref "X1") (pin "1") (pinfunction "1_1") (pintype "passive"))
    )
    (net (code "41") (name "Net-(U4-PB7(XTAL2{slash}TOSC2))") (class "Default")
      (node (ref "U4") (pin "8") (pinfunction "PB7(XTAL2/TOSC2)_8") (pintype "bidirectional"))
      (node (ref "X1") (pin "3") (pinfunction "3_3") (pintype "passive"))
    )
    (net (code "42") (name "RST") (class "Default")
      (node (ref "C24") (pin "2") (pinfunction "2_2") (pintype "passive"))
      (node (ref "R17") (pin "1") (pinfunction "1_1") (pintype "passive"))
      (node (ref "RESET") (pin "P$1") (pinfunction "1_P$1") (pintype "passive"))
      (node (ref "TP4") (pin "TP") (pinfunction "TP_TP") (pintype "input"))
      (node (ref "U4") (pin "29") (pinfunction "PC6(/RESET)_29") (pintype "bidirectional"))
    )
    (net (code "43") (name "SCL") (class "Default")
      (node (ref "R15") (pin "1") (pinfunction "1_1") (pintype "passive"))
      (node (ref "U4") (pin "28") (pinfunction "PC5(ADC5/SCL)_28") (pintype "bidirectional"))
      (node (ref "U5") (pin "6") (pinfunction "SCL_6") (pintype "bidirectional"))
      (node (ref "U6") (pin "4") (pinfunction "SCL_4") (pintype "bidirectional"))
    )
    (net (code "44") (name "SDA") (class "Default")
      (node (ref "R16") (pin "1") (pinfunction "1_1") (pintype "passive"))
      (node (ref "U4") (pin "27") (pinfunction "PC4(ADC4/SDA)_27") (pintype "bidirectional"))
      (node (ref "U5") (pin "1") (pinfunction "SDA_1") (pintype "bidirectional"))
      (node (ref "U6") (pin "6") (pinfunction "SDA_6") (pintype "bidirectional"))
    )
    (net (code "45") (name "VCC3") (class "Default")
      (node (ref "C18") (pin "2") (pinfunction "2_2") (pintype "passive"))
      (node (ref "C19") (pin "2") (pinfunction "2_2") (pintype "passive"))
      (node (ref "C2") (pin "2") (pinfunction "2_2") (pintype "passive"))
      (node (ref "C20") (pin "2") (pinfunction "2_2") (pintype "passive"))
      (node (ref "C21") (pin "2") (pinfunction "2_2") (pintype "passive"))
      (node (ref "C23") (pin "2") (pinfunction "2_2") (pintype "passive"))
      (node (ref "C25") (pin "2") (pinfunction "2_2") (pintype "passive"))
      (node (ref "C26") (pin "2") (pinfunction "2_2") (pintype "passive"))
      (node (ref "C27") (pin "1") (pinfunction "1_1") (pintype "passive"))
      (node (ref "C28") (pin "2") (pinfunction "2_2") (pintype "passive"))
      (node (ref "C29") (pin "1") (pinfunction "1_1") (pintype "passive"))
      (node (ref "C30") (pin "2") (pinfunction "2_2") (pintype "passive"))
      (node (ref "C31") (pin "2") (pinfunction "2_2") (pintype "passive"))
      (node (ref "C32") (pin "2") (pinfunction "2_2") (pintype "passive"))
      (node (ref "C33") (pin "2") (pinfunction "2_2") (pintype "passive"))
      (node (ref "C6") (pin "2") (pinfunction "2_2") (pintype "passive"))
      (node (ref "C7") (pin "2") (pinfunction "2_2") (pintype "passive"))
      (node (ref "JP2") (pin "4") (pinfunction "4_4") (pintype "passive"))
      (node (ref "Q1") (pin "2") (pinfunction "S_2") (pintype "passive"))
      (node (ref "R10") (pin "2") (pinfunction "2_2") (pintype "passive"))
      (node (ref "R11") (pin "1") (pinfunction "1_1") (pintype "passive"))
      (node (ref "R13") (pin "2") (pinfunction "2_2") (pintype "passive"))
      (node (ref "R15") (pin "2") (pinfunction "2_2") (pintype "passive"))
      (node (ref "R16") (pin "2") (pinfunction "2_2") (pintype "passive"))
      (node (ref "R17") (pin "2") (pinfunction "2_2") (pintype "passive"))
      (node (ref "R18") (pin "2") (pinfunction "2_2") (pintype "passive"))
      (node (ref "R19") (pin "1") (pinfunction "1_1") (pintype "passive"))
      (node (ref "R21") (pin "2") (pinfunction "2_2") (pintype "passive"))
      (node (ref "R9") (pin "2") (pinfunction "2_2") (pintype "passive"))
      (node (ref "TP10") (pin "TP") (pinfunction "TP_TP") (pintype "input"))
      (node (ref "U1") (pin "5") (pinfunction "V+_5") (pintype "bidirectional"))
      (node (ref "U2") (pin "8") (pinfunction "V+_8") (pintype "power_in"))
      (node (ref "U3") (pin "5") (pinfunction "V+_5") (pintype "bidirectional"))
      (node (ref "U4") (pin "18") (pinfunction "AVCC_18") (pintype "bidirectional"))
      (node (ref "U4") (pin "4") (pinfunction "VCC_4") (pintype "bidirectional"))
      (node (ref "U4") (pin "6") (pinfunction "VCC_6") (pintype "bidirectional"))
      (node (ref "U5") (pin "5") (pinfunction "VCC_5") (pintype "bidirectional"))
      (node (ref "U6") (pin "1") (pinfunction "VCC_1") (pintype "bidirectional"))
      (node (ref "U7") (pin "HOLD") (pinfunction "~{HOLD}_HOLD") (pintype "input"))
      (node (ref "U7") (pin "VCC") (pinfunction "VCC_VCC") (pintype "power_in"))
      (node (ref "U7") (pin "WP") (pinfunction "~{WP}_WP") (pintype "input"))
      (node (ref "U8") (pin "2") (pinfunction "VCC_2") (pintype "bidirectional"))
      (node (ref "U9") (pin "VDD") (pinfunction "VCC_VDD") (pintype "power_in"))
    )
  )
)
